# biestable.net
KiCad netlist of a schematic drawn in EAGLE
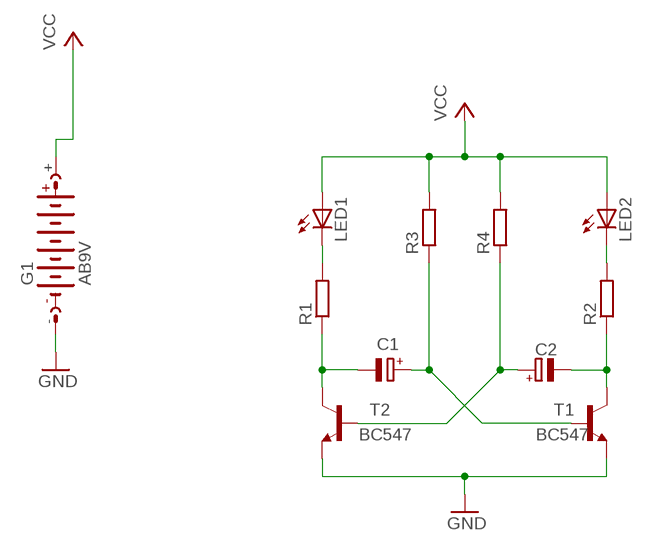
[diagram p0: schematic, sheet 1]

(export (version "E")
  (design (tool "Eeschema 10.0.6"))
  (components
    (comp (ref "C1")
      (value "CPOL-EUE1.8-4")
      (footprint "eagle-import:E1,8-4")
      (libsource (lib "eagle-import") (part "CPOL-EUE1.8-4"))
    )
    (comp (ref "C2")
      (value "CPOL-EUE1.8-4")
      (footprint "eagle-import:E1,8-4")
      (libsource (lib "eagle-import") (part "CPOL-EUE1.8-4"))
    )
    (comp (ref "G1")
      (value "AB9V")
      (footprint "eagle-import:AB9V")
      (libsource (lib "eagle-import") (part "AB9V"))
    )
    (comp (ref "LED1")
      (value "LED5MM")
      (footprint "eagle-import:LED5MM")
      (libsource (lib "eagle-import") (part "LED5MM"))
    )
    (comp (ref "LED2")
      (value "LED5MM")
      (footprint "eagle-import:LED5MM")
      (libsource (lib "eagle-import") (part "LED5MM"))
    )
    (comp (ref "R1")
      (value "R0207/10")
      (footprint "eagle-import:0207_10")
      (libsource (lib "eagle-import") (part "R0207/10"))
    )
    (comp (ref "R2")
      (value "R0207/10")
      (footprint "eagle-import:0207_10")
      (libsource (lib "eagle-import") (part "R0207/10"))
    )
    (comp (ref "R3")
      (value "R0207/10")
      (footprint "eagle-import:0207_10")
      (libsource (lib "eagle-import") (part "R0207/10"))
    )
    (comp (ref "R4")
      (value "R0207/10")
      (footprint "eagle-import:0207_10")
      (libsource (lib "eagle-import") (part "R0207/10"))
    )
    (comp (ref "T1")
      (value "BC547")
      (footprint "eagle-import:TO92")
      (libsource (lib "eagle-import") (part "BC547"))
    )
    (comp (ref "T2")
      (value "BC547")
      (footprint "eagle-import:TO92")
      (libsource (lib "eagle-import") (part "BC547"))
    )
  )
  (nets
    (net (code "1") (name "GND") (class "Default")
      (node (ref "G1") (pin "-") (pinfunction "-_-") (pintype "passive"))
      (node (ref "T1") (pin "1") (pinfunction "E_1") (pintype "passive"))
      (node (ref "T2") (pin "1") (pinfunction "E_1") (pintype "passive"))
    )
    (net (code "2") (name "Net-(LED1-C)") (class "Default")
      (node (ref "LED1") (pin "K") (pinfunction "C_K") (pintype "passive"))
      (node (ref "R1") (pin "2") (pinfunction "2_2") (pintype "passive"))
    )
    (net (code "3") (name "Net-(LED2-C)") (class "Default")
      (node (ref "LED2") (pin "K") (pinfunction "C_K") (pintype "passive"))
      (node (ref "R2") (pin "2") (pinfunction "2_2") (pintype "passive"))
    )
    (net (code "4") (name "Net-(T1-B)") (class "Default")
      (node (ref "C1") (pin "+") (pinfunction "+_+") (pintype "passive"))
      (node (ref "R3") (pin "1") (pinfunction "1_1") (pintype "passive"))
      (node (ref "T1") (pin "2") (pinfunction "B_2") (pintype "passive"))
    )
    (net (code "5") (name "Net-(T1-C)") (class "Default")
      (node (ref "C2") (pin "-") (pinfunction "-_-") (pintype "passive"))
      (node (ref "R2") (pin "1") (pinfunction "1_1") (pintype "passive"))
      (node (ref "T1") (pin "3") (pinfunction "C_3") (pintype "passive"))
    )
    (net (code "6") (name "Net-(T2-B)") (class "Default")
      (node (ref "C2") (pin "+") (pinfunction "+_+") (pintype "passive"))
      (node (ref "R4") (pin "1") (pinfunction "1_1") (pintype "passive"))
      (node (ref "T2") (pin "2") (pinfunction "B_2") (pintype "passive"))
    )
    (net (code "7") (name "Net-(T2-C)") (class "Default")
      (node (ref "C1") (pin "-") (pinfunction "-_-") (pintype "passive"))
      (node (ref "R1") (pin "1") (pinfunction "1_1") (pintype "passive"))
      (node (ref "T2") (pin "3") (pinfunction "C_3") (pintype "passive"))
    )
    (net (code "8") (name "VCC") (class "Default")
      (node (ref "G1") (pin "+") (pinfunction "+_+") (pintype "passive"))
      (node (ref "LED1") (pin "A") (pinfunction "A_A") (pintype "passive"))
      (node (ref "LED2") (pin "A") (pinfunction "A_A") (pintype "passive"))
      (node (ref "R3") (pin "2") (pinfunction "2_2") (pintype "passive"))
      (node (ref "R4") (pin "2") (pinfunction "2_2") (pintype "passive"))
    )
  )
)
